# FP_Connectors.net
KiCad netlist of a schematic drawn in Altium Designer
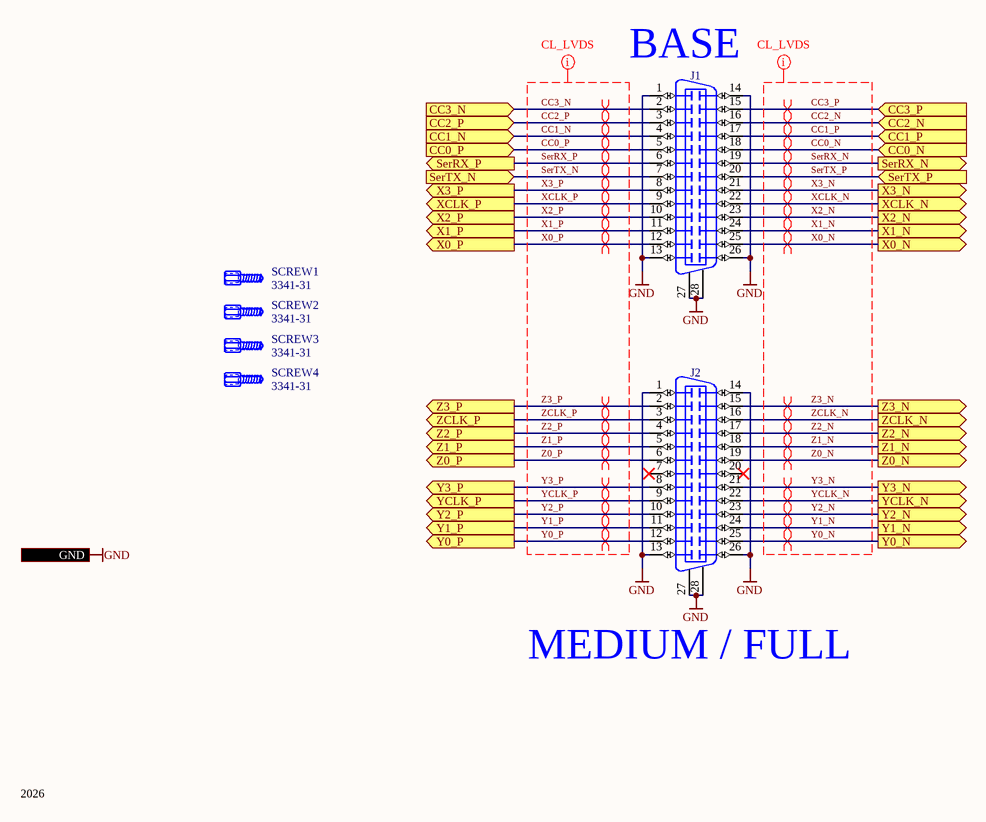
[diagram p0: FP_Connectors.SchDoc]

(export (version "E")
  (design (tool "Eeschema 10.0.6"))
  (components
    (comp (ref "J1")
      (value "N10226-5212PC")
      (footprint "3M_N10226-5212PC")
      (description "Connector Mini D Ribbon (MDR) 26 Female")
      (fields (field (name "MANUFACTURER") "3M") (field (name "AUTHOR") "CERN DEM JLC"))
      (libsource (lib "Connectors") (part "Connector MDR 26 Female"))
    )
    (comp (ref "J2")
      (value "N10226-5212PC")
      (footprint "3M_N10226-5212PC")
      (description "Connector Mini D Ribbon (MDR) 26 Female")
      (fields (field (name "MANUFACTURER") "3M") (field (name "AUTHOR") "CERN DEM JLC"))
      (libsource (lib "Connectors") (part "Connector MDR 26 Female"))
    )
    (comp (ref "SCREW1")
      (value "3341-31")
      (footprint "3M_3341-31")
      (description "VHDCI Female Screw Lock")
      (fields (field (name "MANUFACTURER") "3M") (field (name "AUTHOR") "GK"))
      (libsource (lib "LIBRARY_SCH") (part "MECH_MDR_screw_lock"))
    )
    (comp (ref "SCREW2")
      (value "3341-31")
      (footprint "3M_3341-31")
      (description "VHDCI Female Screw Lock")
      (fields (field (name "MANUFACTURER") "3M") (field (name "AUTHOR") "GK"))
      (libsource (lib "LIBRARY_SCH") (part "MECH_MDR_screw_lock"))
    )
    (comp (ref "SCREW3")
      (value "3341-31")
      (footprint "3M_3341-31")
      (description "VHDCI Female Screw Lock")
      (fields (field (name "MANUFACTURER") "3M") (field (name "AUTHOR") "GK"))
      (libsource (lib "LIBRARY_SCH") (part "MECH_MDR_screw_lock"))
    )
    (comp (ref "SCREW4")
      (value "3341-31")
      (footprint "3M_3341-31")
      (description "VHDCI Female Screw Lock")
      (fields (field (name "MANUFACTURER") "3M") (field (name "AUTHOR") "GK"))
      (libsource (lib "LIBRARY_SCH") (part "MECH_MDR_screw_lock"))
    )
  )
  (nets
    (net (code "1") (name "/CC0_N") (class "Default")
      (node (ref "J1") (pin "18") (pinfunction "18_18") (pintype "bidirectional"))
    )
    (net (code "2") (name "/CC0_P") (class "Default")
      (node (ref "J1") (pin "5") (pinfunction "5_5") (pintype "bidirectional"))
    )
    (net (code "3") (name "/CC1_N") (class "Default")
      (node (ref "J1") (pin "4") (pinfunction "4_4") (pintype "bidirectional"))
    )
    (net (code "4") (name "/CC1_P") (class "Default")
      (node (ref "J1") (pin "17") (pinfunction "17_17") (pintype "bidirectional"))
    )
    (net (code "5") (name "/CC2_N") (class "Default")
      (node (ref "J1") (pin "16") (pinfunction "16_16") (pintype "bidirectional"))
    )
    (net (code "6") (name "/CC2_P") (class "Default")
      (node (ref "J1") (pin "3") (pinfunction "3_3") (pintype "bidirectional"))
    )
    (net (code "7") (name "/CC3_N") (class "Default")
      (node (ref "J1") (pin "2") (pinfunction "2_2") (pintype "bidirectional"))
    )
    (net (code "8") (name "/CC3_P") (class "Default")
      (node (ref "J1") (pin "15") (pinfunction "15_15") (pintype "bidirectional"))
    )
    (net (code "9") (name "/SerRX_N") (class "Default")
      (node (ref "J1") (pin "19") (pinfunction "19_19") (pintype "bidirectional"))
    )
    (net (code "10") (name "/SerRX_P") (class "Default")
      (node (ref "J1") (pin "6") (pinfunction "6_6") (pintype "bidirectional"))
    )
    (net (code "11") (name "/SerTX_N") (class "Default")
      (node (ref "J1") (pin "7") (pinfunction "7_7") (pintype "bidirectional"))
    )
    (net (code "12") (name "/SerTX_P") (class "Default")
      (node (ref "J1") (pin "20") (pinfunction "20_20") (pintype "bidirectional"))
    )
    (net (code "13") (name "/X0_N") (class "Default")
      (node (ref "J1") (pin "25") (pinfunction "25_25") (pintype "bidirectional"))
    )
    (net (code "14") (name "/X0_P") (class "Default")
      (node (ref "J1") (pin "12") (pinfunction "12_12") (pintype "bidirectional"))
    )
    (net (code "15") (name "/X1_N") (class "Default")
      (node (ref "J1") (pin "24") (pinfunction "24_24") (pintype "bidirectional"))
    )
    (net (code "16") (name "/X1_P") (class "Default")
      (node (ref "J1") (pin "11") (pinfunction "11_11") (pintype "bidirectional"))
    )
    (net (code "17") (name "/X2_N") (class "Default")
      (node (ref "J1") (pin "23") (pinfunction "23_23") (pintype "bidirectional"))
    )
    (net (code "18") (name "/X2_P") (class "Default")
      (node (ref "J1") (pin "10") (pinfunction "10_10") (pintype "bidirectional"))
    )
    (net (code "19") (name "/X3_N") (class "Default")
      (node (ref "J1") (pin "21") (pinfunction "21_21") (pintype "bidirectional"))
    )
    (net (code "20") (name "/X3_P") (class "Default")
      (node (ref "J1") (pin "8") (pinfunction "8_8") (pintype "bidirectional"))
    )
    (net (code "21") (name "/XCLK_N") (class "Default")
      (node (ref "J1") (pin "22") (pinfunction "22_22") (pintype "bidirectional"))
    )
    (net (code "22") (name "/XCLK_P") (class "Default")
      (node (ref "J1") (pin "9") (pinfunction "9_9") (pintype "bidirectional"))
    )
    (net (code "23") (name "/Y0_N") (class "Default")
      (node (ref "J2") (pin "25") (pinfunction "25_25") (pintype "bidirectional"))
    )
    (net (code "24") (name "/Y0_P") (class "Default")
      (node (ref "J2") (pin "12") (pinfunction "12_12") (pintype "bidirectional"))
    )
    (net (code "25") (name "/Y1_N") (class "Default")
      (node (ref "J2") (pin "24") (pinfunction "24_24") (pintype "bidirectional"))
    )
    (net (code "26") (name "/Y1_P") (class "Default")
      (node (ref "J2") (pin "11") (pinfunction "11_11") (pintype "bidirectional"))
    )
    (net (code "27") (name "/Y2_N") (class "Default")
      (node (ref "J2") (pin "23") (pinfunction "23_23") (pintype "bidirectional"))
    )
    (net (code "28") (name "/Y2_P") (class "Default")
      (node (ref "J2") (pin "10") (pinfunction "10_10") (pintype "bidirectional"))
    )
    (net (code "29") (name "/Y3_N") (class "Default")
      (node (ref "J2") (pin "21") (pinfunction "21_21") (pintype "bidirectional"))
    )
    (net (code "30") (name "/Y3_P") (class "Default")
      (node (ref "J2") (pin "8") (pinfunction "8_8") (pintype "bidirectional"))
    )
    (net (code "31") (name "/YCLK_N") (class "Default")
      (node (ref "J2") (pin "22") (pinfunction "22_22") (pintype "bidirectional"))
    )
    (net (code "32") (name "/YCLK_P") (class "Default")
      (node (ref "J2") (pin "9") (pinfunction "9_9") (pintype "bidirectional"))
    )
    (net (code "33") (name "/Z0_N") (class "Default")
      (node (ref "J2") (pin "19") (pinfunction "19_19") (pintype "bidirectional"))
    )
    (net (code "34") (name "/Z0_P") (class "Default")
      (node (ref "J2") (pin "6") (pinfunction "6_6") (pintype "bidirectional"))
    )
    (net (code "35") (name "/Z1_N") (class "Default")
      (node (ref "J2") (pin "18") (pinfunction "18_18") (pintype "bidirectional"))
    )
    (net (code "36") (name "/Z1_P") (class "Default")
      (node (ref "J2") (pin "5") (pinfunction "5_5") (pintype "bidirectional"))
    )
    (net (code "37") (name "/Z2_N") (class "Default")
      (node (ref "J2") (pin "17") (pinfunction "17_17") (pintype "bidirectional"))
    )
    (net (code "38") (name "/Z2_P") (class "Default")
      (node (ref "J2") (pin "4") (pinfunction "4_4") (pintype "bidirectional"))
    )
    (net (code "39") (name "/Z3_N") (class "Default")
      (node (ref "J2") (pin "15") (pinfunction "15_15") (pintype "bidirectional"))
    )
    (net (code "40") (name "/Z3_P") (class "Default")
      (node (ref "J2") (pin "2") (pinfunction "2_2") (pintype "bidirectional"))
    )
    (net (code "41") (name "/ZCLK_N") (class "Default")
      (node (ref "J2") (pin "16") (pinfunction "16_16") (pintype "bidirectional"))
    )
    (net (code "42") (name "/ZCLK_P") (class "Default")
      (node (ref "J2") (pin "3") (pinfunction "3_3") (pintype "bidirectional"))
    )
    (net (code "43") (name "GND") (class "Default")
      (node (ref "J1") (pin "1") (pinfunction "1_1") (pintype "bidirectional"))
      (node (ref "J1") (pin "13") (pinfunction "13_13") (pintype "bidirectional"))
      (node (ref "J1") (pin "14") (pinfunction "14_14") (pintype "bidirectional"))
      (node (ref "J1") (pin "26") (pinfunction "26_26") (pintype "bidirectional"))
      (node (ref "J1") (pin "27") (pinfunction "27_27") (pintype "passive"))
      (node (ref "J1") (pin "28") (pinfunction "28_28") (pintype "passive"))
      (node (ref "J2") (pin "1") (pinfunction "1_1") (pintype "bidirectional"))
      (node (ref "J2") (pin "13") (pinfunction "13_13") (pintype "bidirectional"))
      (node (ref "J2") (pin "14") (pinfunction "14_14") (pintype "bidirectional"))
      (node (ref "J2") (pin "26") (pinfunction "26_26") (pintype "bidirectional"))
      (node (ref "J2") (pin "27") (pinfunction "27_27") (pintype "passive"))
      (node (ref "J2") (pin "28") (pinfunction "28_28") (pintype "passive"))
    )
    (net (code "44") (name "unconnected-(J2-Pad7)") (class "Default")
      (node (ref "J2") (pin "7") (pinfunction "7_7") (pintype "bidirectional+no_connect"))
    )
    (net (code "45") (name "unconnected-(J2-Pad20)") (class "Default")
      (node (ref "J2") (pin "20") (pinfunction "20_20") (pintype "bidirectional+no_connect"))
    )
  )
)
